# Elkapod_power_supply_conveter_module.net
KiCad netlist of a schematic drawn in Altium Designer
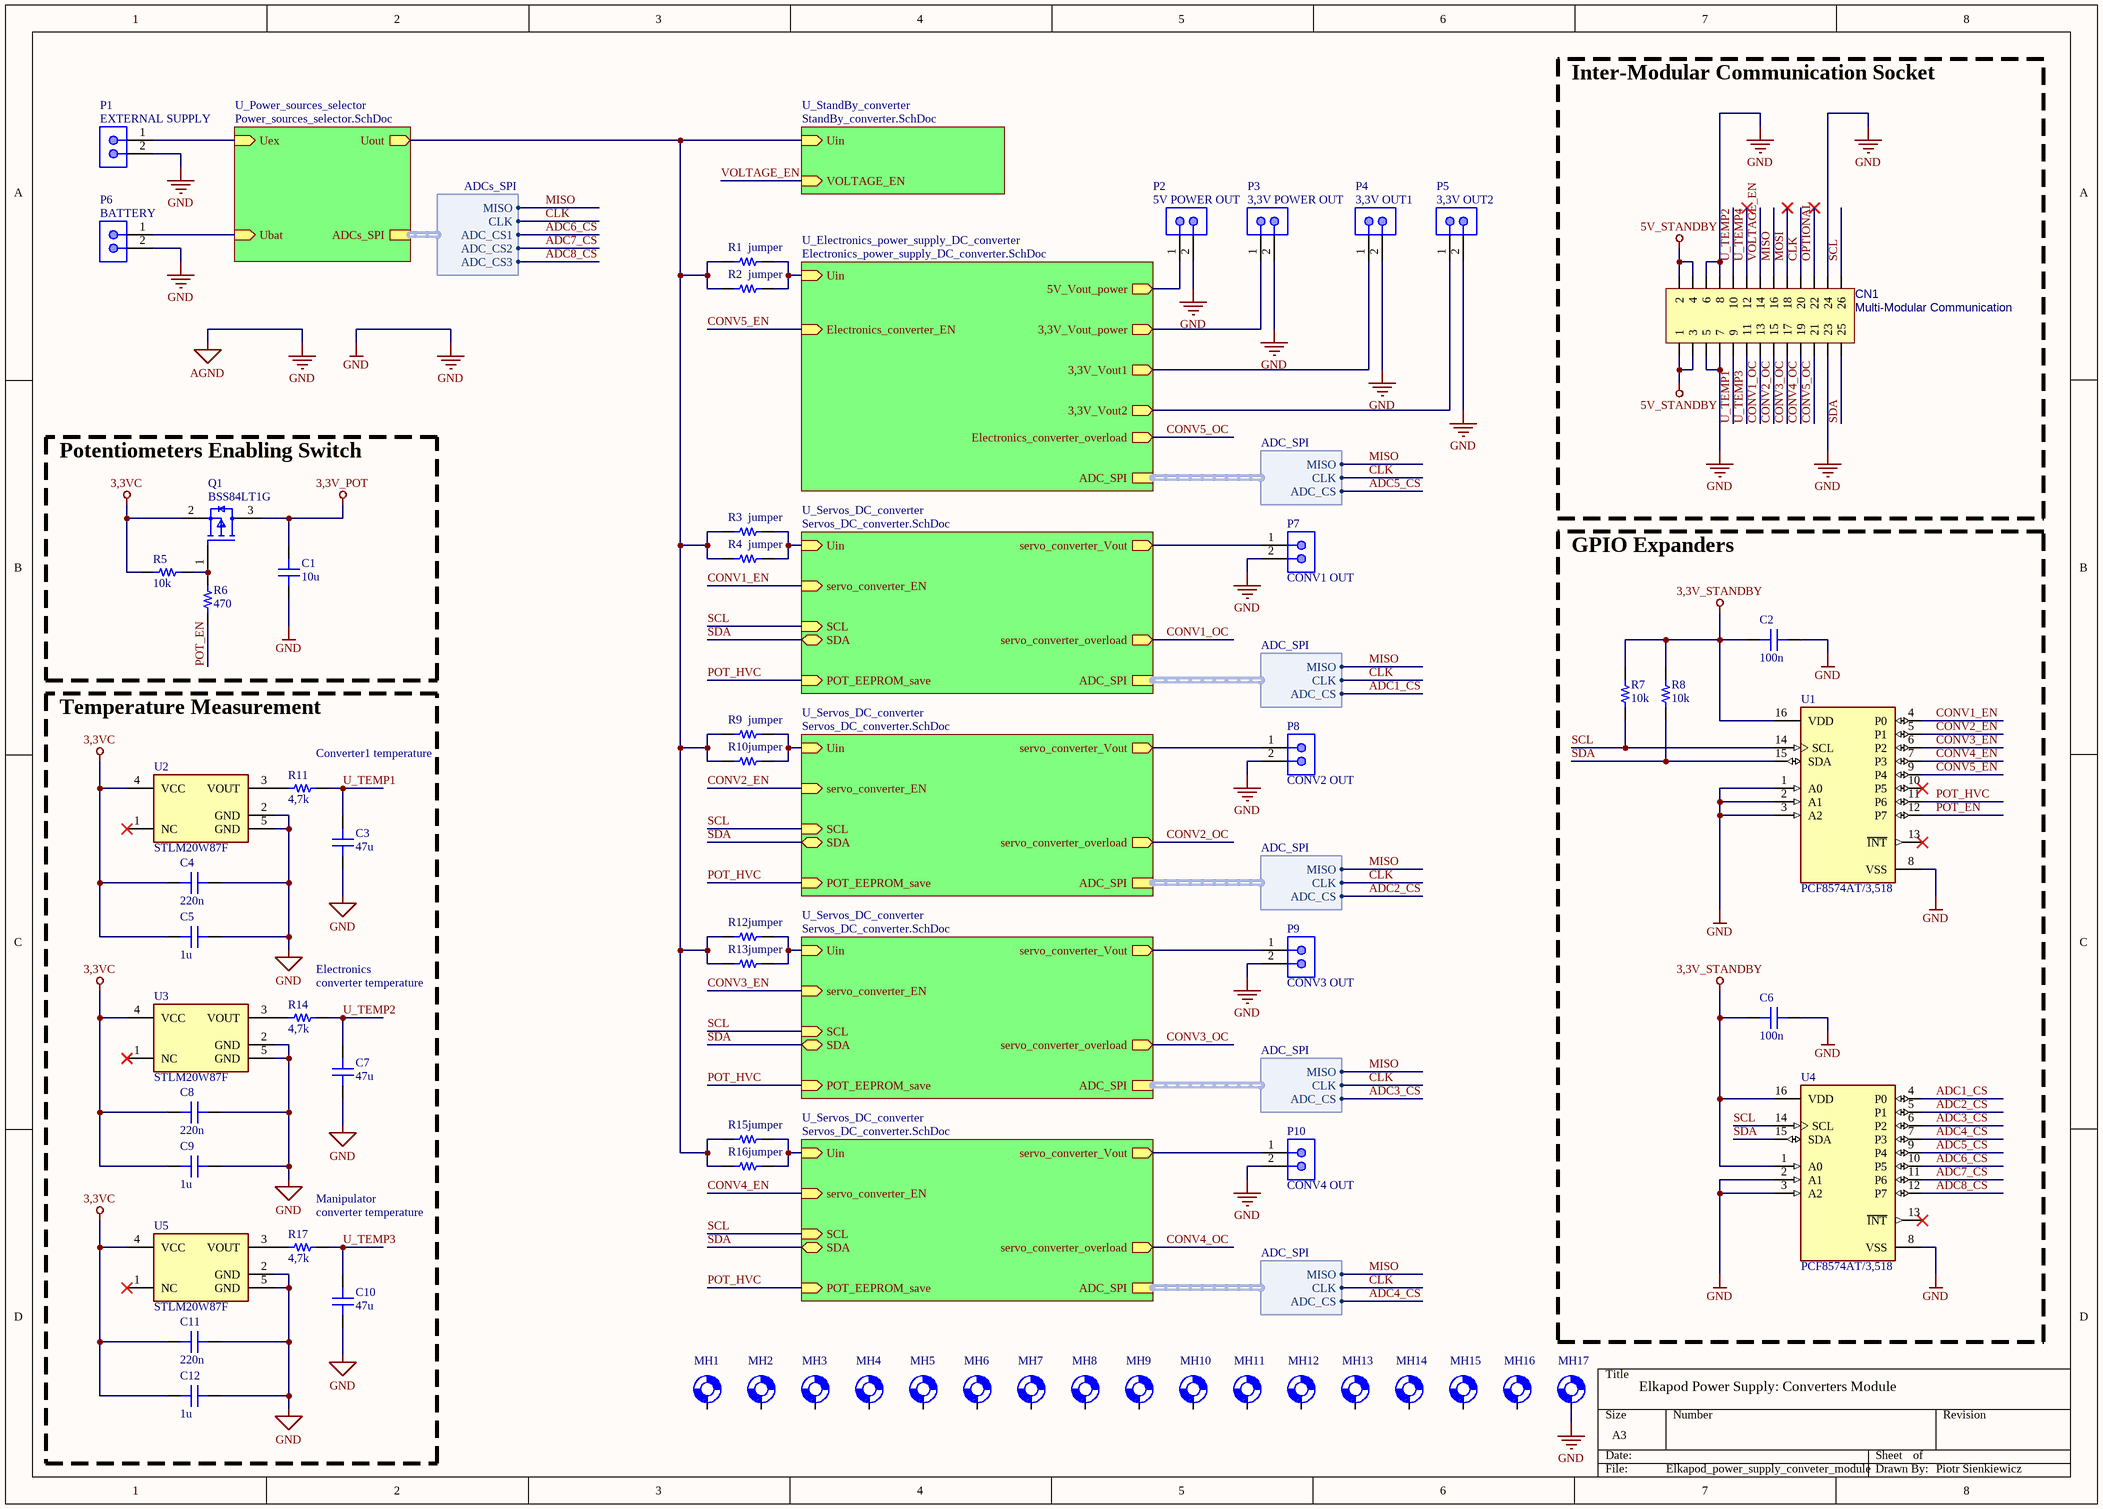
[diagram p0: Elkapod_power_supply_conveter_module.SchDoc]

(export (version "E")
  (design (tool "Eeschema 10.0.6"))
  (components
    (comp (ref "C1")
      (value "10u")
      (footprint "CAP 0603_1608")
      (description "CAP CER 10uF 35V X5R 0603")
      (fields (field (name "PART NUMBER") "C0603C272F3GAC7867") (field (name "MANUFACTURER") "KEMET"))
      (libsource (lib "Celestial Altium Library - altium_library") (part "Capacitor"))
    )
    (comp (ref "C2")
      (value "100n")
      (footprint "CAP 0603_1608")
      (description "CAP CER 100nF 25V X5R 0603")
      (fields (field (name "PART NUMBER") "C0603C272F3GAC7867") (field (name "MANUFACTURER") "KEMET"))
      (libsource (lib "Celestial Altium Library - altium_library") (part "Capacitor"))
    )
    (comp (ref "C3")
      (value "47u")
      (footprint "CAP 0603_1608")
      (description "CAP CER 47uF 6,3V X5R 0603")
      (fields (field (name "PART NUMBER") "C0603C272F3GAC7867") (field (name "MANUFACTURER") "KEMET"))
      (libsource (lib "Celestial Altium Library - altium_library") (part "Capacitor"))
    )
    (comp (ref "C4")
      (value "220n")
      (footprint "CAP 0603_1608")
      (description "CAP CER 220nF 25V X5R 0603")
      (fields (field (name "PART NUMBER") "C0603C272F3GAC7867") (field (name "MANUFACTURER") "KEMET"))
      (libsource (lib "Celestial Altium Library - altium_library") (part "Capacitor"))
    )
    (comp (ref "C5")
      (value "1u")
      (footprint "CAP 0603_1608")
      (description "CAP CER 1uF 25V X5R 0603")
      (fields (field (name "PART NUMBER") "C0603C272F3GAC7867") (field (name "MANUFACTURER") "KEMET"))
      (libsource (lib "Celestial Altium Library - altium_library") (part "Capacitor"))
    )
    (comp (ref "C6")
      (value "100n")
      (footprint "CAP 0603_1608")
      (description "CAP CER 100nF 25V X5R 0603")
      (fields (field (name "PART NUMBER") "C0603C272F3GAC7867") (field (name "MANUFACTURER") "KEMET"))
      (libsource (lib "Celestial Altium Library - altium_library") (part "Capacitor"))
    )
    (comp (ref "C7")
      (value "47u")
      (footprint "CAP 0603_1608")
      (description "CAP CER 47uF 6,3V X5R 0603")
      (fields (field (name "PART NUMBER") "C0603C272F3GAC7867") (field (name "MANUFACTURER") "KEMET"))
      (libsource (lib "Celestial Altium Library - altium_library") (part "Capacitor"))
    )
    (comp (ref "C8")
      (value "220n")
      (footprint "CAP 0603_1608")
      (description "CAP CER 220nF 25V X5R 0603")
      (fields (field (name "PART NUMBER") "C0603C272F3GAC7867") (field (name "MANUFACTURER") "KEMET"))
      (libsource (lib "Celestial Altium Library - altium_library") (part "Capacitor"))
    )
    (comp (ref "C9")
      (value "1u")
      (footprint "CAP 0603_1608")
      (description "CAP CER 1uF 25V X5R 0603")
      (fields (field (name "PART NUMBER") "C0603C272F3GAC7867") (field (name "MANUFACTURER") "KEMET"))
      (libsource (lib "Celestial Altium Library - altium_library") (part "Capacitor"))
    )
    (comp (ref "C10")
      (value "47u")
      (footprint "CAP 0603_1608")
      (description "CAP CER 47uF 6,3V X5R 0603")
      (fields (field (name "PART NUMBER") "C0603C272F3GAC7867") (field (name "MANUFACTURER") "KEMET"))
      (libsource (lib "Celestial Altium Library - altium_library") (part "Capacitor"))
    )
    (comp (ref "C11")
      (value "220n")
      (footprint "CAP 0603_1608")
      (description "CAP CER 220nF 25V X5R 0603")
      (fields (field (name "PART NUMBER") "C0603C272F3GAC7867") (field (name "MANUFACTURER") "KEMET"))
      (libsource (lib "Celestial Altium Library - altium_library") (part "Capacitor"))
    )
    (comp (ref "C12")
      (value "1u")
      (footprint "CAP 0603_1608")
      (description "CAP CER 1uF 25V X5R 0603")
      (fields (field (name "PART NUMBER") "C0603C272F3GAC7867") (field (name "MANUFACTURER") "KEMET"))
      (libsource (lib "Celestial Altium Library - altium_library") (part "Capacitor"))
    )
    (comp (ref "CN1")
      (value "Multi-Modular Communication")
      (footprint "GP_13x2_F")
      (libsource (lib "goldpin_female") (part "CN_13x2"))
    )
    (comp (ref "MH1")
      (value "M3 Mounting Hole")
      (footprint "M3_MOUNTING_HOLE")
      (libsource (lib "My_mounting_components") (part "M3 Mounting Hole"))
    )
    (comp (ref "MH2")
      (value "M3 Mounting Hole")
      (footprint "M3_MOUNTING_HOLE")
      (libsource (lib "My_mounting_components") (part "M3 Mounting Hole"))
    )
    (comp (ref "MH3")
      (value "M3 Mounting Hole")
      (footprint "M3_MOUNTING_HOLE")
      (libsource (lib "My_mounting_components") (part "M3 Mounting Hole"))
    )
    (comp (ref "MH4")
      (value "M3 Mounting Hole")
      (footprint "M3_MOUNTING_HOLE")
      (libsource (lib "My_mounting_components") (part "M3 Mounting Hole"))
    )
    (comp (ref "MH5")
      (value "M3 Mounting Hole")
      (footprint "M3_MOUNTING_HOLE")
      (libsource (lib "My_mounting_components") (part "M3 Mounting Hole"))
    )
    (comp (ref "MH6")
      (value "M3 Mounting Hole")
      (footprint "M3_MOUNTING_HOLE")
      (libsource (lib "My_mounting_components") (part "M3 Mounting Hole"))
    )
    (comp (ref "MH7")
      (value "M3 Mounting Hole")
      (footprint "M3_MOUNTING_HOLE")
      (libsource (lib "My_mounting_components") (part "M3 Mounting Hole"))
    )
    (comp (ref "MH8")
      (value "M3 Mounting Hole")
      (footprint "M3_MOUNTING_HOLE")
      (libsource (lib "My_mounting_components") (part "M3 Mounting Hole"))
    )
    (comp (ref "MH9")
      (value "M3 Mounting Hole")
      (footprint "M3_MOUNTING_HOLE")
      (libsource (lib "My_mounting_components") (part "M3 Mounting Hole"))
    )
    (comp (ref "MH10")
      (value "M3 Mounting Hole")
      (footprint "M3_MOUNTING_HOLE")
      (libsource (lib "My_mounting_components") (part "M3 Mounting Hole"))
    )
    (comp (ref "MH11")
      (value "M3 Mounting Hole")
      (footprint "M3_MOUNTING_HOLE")
      (libsource (lib "My_mounting_components") (part "M3 Mounting Hole"))
    )
    (comp (ref "MH12")
      (value "M3 Mounting Hole")
      (footprint "M3_MOUNTING_HOLE")
      (libsource (lib "My_mounting_components") (part "M3 Mounting Hole"))
    )
    (comp (ref "MH13")
      (value "M3 Mounting Hole")
      (footprint "M3_MOUNTING_HOLE")
      (libsource (lib "My_mounting_components") (part "M3 Mounting Hole"))
    )
    (comp (ref "MH14")
      (value "M3 Mounting Hole")
      (footprint "M3_MOUNTING_HOLE")
      (libsource (lib "My_mounting_components") (part "M3 Mounting Hole"))
    )
    (comp (ref "MH15")
      (value "M3 Mounting Hole")
      (footprint "M3_MOUNTING_HOLE")
      (libsource (lib "My_mounting_components") (part "M3 Mounting Hole"))
    )
    (comp (ref "MH16")
      (value "M3 Mounting Hole")
      (footprint "M3_MOUNTING_HOLE")
      (libsource (lib "My_mounting_components") (part "M3 Mounting Hole"))
    )
    (comp (ref "MH17")
      (value "M3 Mounting Hole")
      (footprint "M3_MOUNTING_HOLE")
      (libsource (lib "My_mounting_components") (part "M3 Mounting Hole"))
    )
    (comp (ref "P1")
      (value "EXTERNAL SUPPLY")
      (footprint "XT60PB-M")
      (description "XT60UPB-M; 30A/500V straight female DC PCB socket (pin1 -> +, pin2 -> -)")
      (libsource (lib "My_sockets") (part "XT60PB-M"))
    )
    (comp (ref "P2")
      (value "5V POWER OUT")
      (footprint "2x2,5mm2_WIRE")
      (description "2x2,5mm2 wire pads")
      (libsource (lib "") (part "2X2,5mm2_WIRE_1"))
    )
    (comp (ref "P3")
      (value "3,3V POWER OUT")
      (footprint "2x2,5mm2_WIRE")
      (description "2x2,5mm2 wire pads")
      (libsource (lib "") (part "2X2,5mm2_WIRE_1"))
    )
    (comp (ref "P4")
      (value "3,3V OUT1")
      (footprint "2x2,5mm2_WIRE")
      (description "2x2,5mm2 wire pads")
      (libsource (lib "") (part "2X2,5mm2_WIRE_1"))
    )
    (comp (ref "P5")
      (value "3,3V OUT2")
      (footprint "2x2,5mm2_WIRE")
      (description "2x2,5mm2 wire pads")
      (libsource (lib "") (part "2X2,5mm2_WIRE_1"))
    )
    (comp (ref "P6")
      (value "BATTERY")
      (footprint "XT60PB-M")
      (description "XT60UPB-M; 30A/500V straight female DC PCB socket (pin1 -> +, pin2 -> -)")
      (libsource (lib "My_sockets") (part "XT60PB-M"))
    )
    (comp (ref "P7")
      (value "CONV1 OUT")
      (footprint "2x2,5mm2_WIRE")
      (description "2x2,5mm2 wire pads")
      (libsource (lib "My_sockets") (part "2X2,5mm2_WIRE"))
    )
    (comp (ref "P8")
      (value "CONV2 OUT")
      (footprint "2x2,5mm2_WIRE")
      (description "2x2,5mm2 wire pads")
      (libsource (lib "My_sockets") (part "2X2,5mm2_WIRE"))
    )
    (comp (ref "P9")
      (value "CONV3 OUT")
      (footprint "2x2,5mm2_WIRE")
      (description "2x2,5mm2 wire pads")
      (libsource (lib "My_sockets") (part "2X2,5mm2_WIRE"))
    )
    (comp (ref "P10")
      (value "CONV4 OUT")
      (footprint "2x2,5mm2_WIRE")
      (description "2x2,5mm2 wire pads")
      (libsource (lib "My_sockets") (part "2X2,5mm2_WIRE"))
    )
    (comp (ref "Q1")
      (value "BSS84LT1G")
      (footprint "FP-318-08-IPC_A")
      (description "MOSFET P-CH 50V 130MA SOT-23")
      (libsource (lib "Altium Content Vault") (part "1317a8eff0fddff9cd18bdaa032127a"))
    )
    (comp (ref "R1")
      (value "jumper")
      (footprint "STACKPOLE CSM2512")
      (description "RES 0 OHM 1W 2512")
      (fields
        (field (name "PART NUMBER") "CSM2512FT20L0")
        (field (name "MANUFACTURER") "Stackpole Electronics Inc")
      )
      (libsource (lib "Celestial Altium Library - altium_library") (part "Resistor"))
    )
    (comp (ref "R2")
      (value "jumper")
      (footprint "STACKPOLE CSM2512")
      (description "RES 0 OHM 1W 2512")
      (fields
        (field (name "PART NUMBER") "CSM2512FT20L0")
        (field (name "MANUFACTURER") "Stackpole Electronics Inc")
      )
      (libsource (lib "Celestial Altium Library - altium_library") (part "Resistor"))
    )
    (comp (ref "R3")
      (value "jumper")
      (footprint "STACKPOLE CSM2512")
      (description "RES 0 OHM 1W 2512")
      (fields
        (field (name "PART NUMBER") "CSM2512FT20L0")
        (field (name "MANUFACTURER") "Stackpole Electronics Inc")
      )
      (libsource (lib "Celestial Altium Library - altium_library") (part "Resistor"))
    )
    (comp (ref "R4")
      (value "jumper")
      (footprint "STACKPOLE CSM2512")
      (description "RES 0 OHM 1W 2512")
      (fields
        (field (name "PART NUMBER") "CSM2512FT20L0")
        (field (name "MANUFACTURER") "Stackpole Electronics Inc")
      )
      (libsource (lib "Celestial Altium Library - altium_library") (part "Resistor"))
    )
    (comp (ref "R5")
      (value "10k")
      (footprint "RES 0603_1608")
      (description "RES 10K OHM 1% 0,1W 0603")
      (fields
        (field (name "PART NUMBER") "RNCS0603BKE10K0")
        (field (name "MANUFACTURER") "Stackpole Electronics Inc")
      )
      (libsource (lib "Celestial Altium Library - altium_library") (part "Resistor"))
    )
    (comp (ref "R6")
      (value "470")
      (footprint "RES 0603_1608")
      (description "RES 470 OHM 1% 0,1W 0603")
      (fields
        (field (name "PART NUMBER") "RNCS0603BKE10K0")
        (field (name "MANUFACTURER") "Stackpole Electronics Inc")
      )
      (libsource (lib "Celestial Altium Library - altium_library") (part "Resistor"))
    )
    (comp (ref "R7")
      (value "10k")
      (footprint "RES 0603_1608")
      (description "RES 10K OHM 1% 0,1W 0603")
      (fields
        (field (name "PART NUMBER") "RNCS0603BKE10K0")
        (field (name "MANUFACTURER") "Stackpole Electronics Inc")
      )
      (libsource (lib "Celestial Altium Library - altium_library") (part "Resistor"))
    )
    (comp (ref "R8")
      (value "10k")
      (footprint "RES 0603_1608")
      (description "RES 10K OHM 1% 0,1W 0603")
      (fields
        (field (name "PART NUMBER") "RNCS0603BKE10K0")
        (field (name "MANUFACTURER") "Stackpole Electronics Inc")
      )
      (libsource (lib "Celestial Altium Library - altium_library") (part "Resistor"))
    )
    (comp (ref "R9")
      (value "jumper")
      (footprint "STACKPOLE CSM2512")
      (description "RES 0 OHM 1W 2512")
      (fields
        (field (name "PART NUMBER") "CSM2512FT20L0")
        (field (name "MANUFACTURER") "Stackpole Electronics Inc")
      )
      (libsource (lib "Celestial Altium Library - altium_library") (part "Resistor"))
    )
    (comp (ref "R10")
      (value "jumper")
      (footprint "STACKPOLE CSM2512")
      (description "RES 0 OHM 1W 2512")
      (fields
        (field (name "PART NUMBER") "CSM2512FT20L0")
        (field (name "MANUFACTURER") "Stackpole Electronics Inc")
      )
      (libsource (lib "Celestial Altium Library - altium_library") (part "Resistor"))
    )
    (comp (ref "R11")
      (value "4,7k")
      (footprint "RES 0603_1608")
      (description "RES 4,7K OHM 1% 0,1W 0603")
      (fields
        (field (name "PART NUMBER") "RNCS0603BKE10K0")
        (field (name "MANUFACTURER") "Stackpole Electronics Inc")
      )
      (libsource (lib "Celestial Altium Library - altium_library") (part "Resistor"))
    )
    (comp (ref "R12")
      (value "jumper")
      (footprint "STACKPOLE CSM2512")
      (description "RES 0 OHM 1W 2512")
      (fields
        (field (name "PART NUMBER") "CSM2512FT20L0")
        (field (name "MANUFACTURER") "Stackpole Electronics Inc")
      )
      (libsource (lib "Celestial Altium Library - altium_library") (part "Resistor"))
    )
    (comp (ref "R13")
      (value "jumper")
      (footprint "STACKPOLE CSM2512")
      (description "RES 0 OHM 1W 2512")
      (fields
        (field (name "PART NUMBER") "CSM2512FT20L0")
        (field (name "MANUFACTURER") "Stackpole Electronics Inc")
      )
      (libsource (lib "Celestial Altium Library - altium_library") (part "Resistor"))
    )
    (comp (ref "R14")
      (value "4,7k")
      (footprint "RES 0603_1608")
      (description "RES 4,7K OHM 1% 0,1W 0603")
      (fields
        (field (name "PART NUMBER") "RNCS0603BKE10K0")
        (field (name "MANUFACTURER") "Stackpole Electronics Inc")
      )
      (libsource (lib "Celestial Altium Library - altium_library") (part "Resistor"))
    )
    (comp (ref "R15")
      (value "jumper")
      (footprint "STACKPOLE CSM2512")
      (description "RES 0 OHM 1W 2512")
      (fields
        (field (name "PART NUMBER") "CSM2512FT20L0")
        (field (name "MANUFACTURER") "Stackpole Electronics Inc")
      )
      (libsource (lib "Celestial Altium Library - altium_library") (part "Resistor"))
    )
    (comp (ref "R16")
      (value "jumper")
      (footprint "STACKPOLE CSM2512")
      (description "RES 0 OHM 1W 2512")
      (fields
        (field (name "PART NUMBER") "CSM2512FT20L0")
        (field (name "MANUFACTURER") "Stackpole Electronics Inc")
      )
      (libsource (lib "Celestial Altium Library - altium_library") (part "Resistor"))
    )
    (comp (ref "R17")
      (value "4,7k")
      (footprint "RES 0603_1608")
      (description "RES 4,7K OHM 1% 0,1W 0603")
      (fields
        (field (name "PART NUMBER") "RNCS0603BKE10K0")
        (field (name "MANUFACTURER") "Stackpole Electronics Inc")
      )
      (libsource (lib "Celestial Altium Library - altium_library") (part "Resistor"))
    )
    (comp (ref "U1")
      (value "PCF8574AT/3,518")
      (footprint "FP-SOT162-1-MFG")
      (description "IC I/O EXPANDER I2C 8B 16SOIC")
      (fields
        (field (name "MANUFACTURER") "NXP Semiconductors")
        (field (name "OCTOPART") "https://octopart.com/pcf8574at%2F3%2C518-nxp+semiconductors-11541925")
      )
      (libsource (lib "Altium Content Vault") (part "f7fde53ce59de981fb0b266a4e103eb"))
    )
    (comp (ref "U2")
      (value "STLM20W87F")
      (footprint "FP-SOT323-5L-7091413-MFG")
      (description "SENSOR ANALOG -55C-130C SOT323-5")
      (fields
        (field (name "MANUFACTURER") "STMicroelectronics")
        (field (name "OCTOPART") "https://octopart.com/stlm20w87f-stmicroelectronics-4006294")
      )
      (libsource (lib "Altium Content Vault") (part "0e0d9f6345b04f04d846d3fd79e931c"))
    )
    (comp (ref "U3")
      (value "STLM20W87F")
      (footprint "FP-SOT323-5L-7091413-MFG")
      (description "SENSOR ANALOG -55C-130C SOT323-5")
      (fields
        (field (name "MANUFACTURER") "STMicroelectronics")
        (field (name "OCTOPART") "https://octopart.com/stlm20w87f-stmicroelectronics-4006294")
      )
      (libsource (lib "Altium Content Vault") (part "0e0d9f6345b04f04d846d3fd79e931c"))
    )
    (comp (ref "U4")
      (value "PCF8574AT/3,518")
      (footprint "FP-SOT162-1-MFG")
      (description "IC I/O EXPANDER I2C 8B 16SOIC")
      (fields
        (field (name "MANUFACTURER") "NXP Semiconductors")
        (field (name "OCTOPART") "https://octopart.com/pcf8574at%2F3%2C518-nxp+semiconductors-11541925")
      )
      (libsource (lib "Altium Content Vault") (part "f7fde53ce59de981fb0b266a4e103eb"))
    )
    (comp (ref "U5")
      (value "STLM20W87F")
      (footprint "FP-SOT323-5L-7091413-MFG")
      (description "SENSOR ANALOG -55C-130C SOT323-5")
      (fields
        (field (name "MANUFACTURER") "STMicroelectronics")
        (field (name "OCTOPART") "https://octopart.com/stlm20w87f-stmicroelectronics-4006294")
      )
      (libsource (lib "Altium Content Vault") (part "0e0d9f6345b04f04d846d3fd79e931c"))
    )
  )
  (nets
    (net (code "3") (name "/3,3V_Vout1") (class "Default")
      (node (ref "P4") (pin "1") (pinfunction "+_1") (pintype "passive"))
    )
    (net (code "4") (name "/3,3V_Vout2") (class "Default")
      (node (ref "P5") (pin "1") (pinfunction "+_1") (pintype "passive"))
    )
    (net (code "5") (name "/3,3V_Vout_power") (class "Default")
      (node (ref "P3") (pin "1") (pinfunction "+_1") (pintype "passive"))
    )
    (net (code "6") (name "/5V_Vout_power") (class "Default")
      (node (ref "P2") (pin "1") (pinfunction "+_1") (pintype "passive"))
    )
    (net (code "7") (name "/ADC1_CS") (class "Default")
      (node (ref "U4") (pin "4") (pinfunction "P0_4") (pintype "bidirectional"))
    )
    (net (code "8") (name "/ADC2_CS") (class "Default")
      (node (ref "U4") (pin "5") (pinfunction "P1_5") (pintype "bidirectional"))
    )
    (net (code "9") (name "/ADC3_CS") (class "Default")
      (node (ref "U4") (pin "6") (pinfunction "P2_6") (pintype "bidirectional"))
    )
    (net (code "10") (name "/ADC4_CS") (class "Default")
      (node (ref "U4") (pin "7") (pinfunction "P3_7") (pintype "bidirectional"))
    )
    (net (code "11") (name "/ADC5_CS") (class "Default")
      (node (ref "U4") (pin "9") (pinfunction "P4_9") (pintype "bidirectional"))
    )
    (net (code "12") (name "/ADC6_CS") (class "Default")
      (node (ref "U4") (pin "10") (pinfunction "P5_10") (pintype "bidirectional"))
    )
    (net (code "13") (name "/ADC7_CS") (class "Default")
      (node (ref "U4") (pin "11") (pinfunction "P6_11") (pintype "bidirectional"))
    )
    (net (code "14") (name "/ADC8_CS") (class "Default")
      (node (ref "U4") (pin "12") (pinfunction "P7_12") (pintype "bidirectional"))
    )
    (net (code "15") (name "/CLK") (class "Default")
      (node (ref "CN1") (pin "20") (pinfunction "20_20") (pintype "passive"))
    )
    (net (code "16") (name "/CONV1_EN") (class "Default")
      (node (ref "U1") (pin "4") (pinfunction "P0_4") (pintype "bidirectional"))
    )
    (net (code "17") (name "/CONV1_OC") (class "Default")
      (node (ref "CN1") (pin "13") (pinfunction "13_13") (pintype "passive"))
    )
    (net (code "18") (name "/CONV2_EN") (class "Default")
      (node (ref "U1") (pin "5") (pinfunction "P1_5") (pintype "bidirectional"))
    )
    (net (code "19") (name "/CONV2_OC") (class "Default")
      (node (ref "CN1") (pin "15") (pinfunction "15_15") (pintype "passive"))
    )
    (net (code "20") (name "/CONV3_EN") (class "Default")
      (node (ref "U1") (pin "6") (pinfunction "P2_6") (pintype "bidirectional"))
    )
    (net (code "21") (name "/CONV3_OC") (class "Default")
      (node (ref "CN1") (pin "17") (pinfunction "17_17") (pintype "passive"))
    )
    (net (code "22") (name "/CONV4_EN") (class "Default")
      (node (ref "U1") (pin "7") (pinfunction "P3_7") (pintype "bidirectional"))
    )
    (net (code "23") (name "/CONV4_OC") (class "Default")
      (node (ref "CN1") (pin "19") (pinfunction "19_19") (pintype "passive"))
    )
    (net (code "24") (name "/CONV5_EN") (class "Default")
      (node (ref "U1") (pin "9") (pinfunction "P4_9") (pintype "bidirectional"))
    )
    (net (code "25") (name "/CONV5_OC") (class "Default")
      (node (ref "CN1") (pin "21") (pinfunction "21_21") (pintype "passive"))
    )
    (net (code "26") (name "/MISO") (class "Default")
      (node (ref "CN1") (pin "16") (pinfunction "16_16") (pintype "passive"))
    )
    (net (code "27") (name "/MOSI") (class "Default")
      (node (ref "CN1") (pin "18") (pinfunction "18_18") (pintype "passive+no_connect"))
    )
    (net (code "28") (name "/OPTIONAL") (class "Default")
      (node (ref "CN1") (pin "22") (pinfunction "22_22") (pintype "passive+no_connect"))
    )
    (net (code "29") (name "/POT_EN") (class "Default")
      (node (ref "R6") (pin "2") (pinfunction "2_2") (pintype "passive"))
      (node (ref "U1") (pin "12") (pinfunction "P7_12") (pintype "bidirectional"))
    )
    (net (code "30") (name "/POT_HVC") (class "Default")
      (node (ref "U1") (pin "11") (pinfunction "P6_11") (pintype "bidirectional"))
    )
    (net (code "31") (name "/SCL") (class "Default")
      (node (ref "CN1") (pin "26") (pinfunction "26_26") (pintype "passive"))
      (node (ref "R7") (pin "1") (pinfunction "1_1") (pintype "passive"))
      (node (ref "U1") (pin "14") (pinfunction "SCL_14") (pintype "input"))
      (node (ref "U4") (pin "14") (pinfunction "SCL_14") (pintype "input"))
    )
    (net (code "32") (name "/SDA") (class "Default")
      (node (ref "CN1") (pin "25") (pinfunction "25_25") (pintype "passive"))
      (node (ref "R8") (pin "1") (pinfunction "1_1") (pintype "passive"))
      (node (ref "U1") (pin "15") (pinfunction "SDA_15") (pintype "bidirectional"))
      (node (ref "U4") (pin "15") (pinfunction "SDA_15") (pintype "bidirectional"))
    )
    (net (code "33") (name "/U_TEMP1") (class "Default")
      (node (ref "C3") (pin "2") (pinfunction "2_2") (pintype "passive"))
      (node (ref "CN1") (pin "9") (pinfunction "9_9") (pintype "passive"))
      (node (ref "R11") (pin "2") (pinfunction "2_2") (pintype "passive"))
    )
    (net (code "34") (name "/U_TEMP2") (class "Default")
      (node (ref "C7") (pin "2") (pinfunction "2_2") (pintype "passive"))
      (node (ref "CN1") (pin "10") (pinfunction "10_10") (pintype "passive"))
      (node (ref "R14") (pin "2") (pinfunction "2_2") (pintype "passive"))
    )
    (net (code "35") (name "/U_TEMP3") (class "Default")
      (node (ref "C10") (pin "2") (pinfunction "2_2") (pintype "passive"))
      (node (ref "CN1") (pin "11") (pinfunction "11_11") (pintype "passive"))
      (node (ref "R17") (pin "2") (pinfunction "2_2") (pintype "passive"))
    )
    (net (code "36") (name "/U_TEMP4") (class "Default")
      (node (ref "CN1") (pin "12") (pinfunction "12_12") (pintype "passive+no_connect"))
    )
    (net (code "37") (name "/Ubat") (class "Default")
      (node (ref "P6") (pin "1") (pinfunction "+_1") (pintype "passive"))
    )
    (net (code "38") (name "/Uex") (class "Default")
      (node (ref "P1") (pin "1") (pinfunction "+_1") (pintype "passive"))
    )
    (net (code "39") (name "/Uin") (class "Default")
      (node (ref "R1") (pin "1") (pinfunction "1_1") (pintype "passive"))
      (node (ref "R2") (pin "1") (pinfunction "1_1") (pintype "passive"))
    )
    (net (code "40") (name "/Uin_1") (class "Default")
      (node (ref "R3") (pin "1") (pinfunction "1_1") (pintype "passive"))
      (node (ref "R4") (pin "1") (pinfunction "1_1") (pintype "passive"))
    )
    (net (code "41") (name "/Uin_2") (class "Default")
      (node (ref "R12") (pin "1") (pinfunction "1_1") (pintype "passive"))
      (node (ref "R13") (pin "1") (pinfunction "1_1") (pintype "passive"))
    )
    (net (code "42") (name "/Uin_3") (class "Default")
      (node (ref "R15") (pin "1") (pinfunction "1_1") (pintype "passive"))
      (node (ref "R16") (pin "1") (pinfunction "1_1") (pintype "passive"))
    )
    (net (code "43") (name "/Uin_4") (class "Default")
      (node (ref "R10") (pin "1") (pinfunction "1_1") (pintype "passive"))
      (node (ref "R9") (pin "1") (pinfunction "1_1") (pintype "passive"))
    )
    (net (code "44") (name "/Uout") (class "Default")
      (node (ref "R1") (pin "2") (pinfunction "2_2") (pintype "passive"))
      (node (ref "R10") (pin "2") (pinfunction "2_2") (pintype "passive"))
      (node (ref "R12") (pin "2") (pinfunction "2_2") (pintype "passive"))
      (node (ref "R13") (pin "2") (pinfunction "2_2") (pintype "passive"))
      (node (ref "R15") (pin "2") (pinfunction "2_2") (pintype "passive"))
      (node (ref "R16") (pin "2") (pinfunction "2_2") (pintype "passive"))
      (node (ref "R2") (pin "2") (pinfunction "2_2") (pintype "passive"))
      (node (ref "R3") (pin "2") (pinfunction "2_2") (pintype "passive"))
      (node (ref "R4") (pin "2") (pinfunction "2_2") (pintype "passive"))
      (node (ref "R9") (pin "2") (pinfunction "2_2") (pintype "passive"))
    )
    (net (code "45") (name "/VOLTAGE_EN") (class "Default")
      (node (ref "CN1") (pin "14") (pinfunction "14_14") (pintype "passive"))
    )
    (net (code "46") (name "/servo_converter_Vout") (class "Default")
      (node (ref "P10") (pin "1") (pinfunction "+_1") (pintype "passive"))
    )
    (net (code "47") (name "/servo_converter_Vout_1") (class "Default")
      (node (ref "P9") (pin "1") (pinfunction "+_1") (pintype "passive"))
    )
    (net (code "48") (name "/servo_converter_Vout_2") (class "Default")
      (node (ref "P7") (pin "1") (pinfunction "+_1") (pintype "passive"))
    )
    (net (code "49") (name "/servo_converter_Vout_3") (class "Default")
      (node (ref "P8") (pin "1") (pinfunction "+_1") (pintype "passive"))
    )
    (net (code "52") (name "3,3VC") (class "Default")
      (node (ref "C11") (pin "2") (pinfunction "2_2") (pintype "passive"))
      (node (ref "C12") (pin "2") (pinfunction "2_2") (pintype "passive"))
      (node (ref "C4") (pin "2") (pinfunction "2_2") (pintype "passive"))
      (node (ref "C5") (pin "2") (pinfunction "2_2") (pintype "passive"))
      (node (ref "C8") (pin "2") (pinfunction "2_2") (pintype "passive"))
      (node (ref "C9") (pin "2") (pinfunction "2_2") (pintype "passive"))
      (node (ref "Q1") (pin "2") (pinfunction "S_2") (pintype "passive"))
      (node (ref "R5") (pin "1") (pinfunction "1_1") (pintype "passive"))
      (node (ref "U2") (pin "4") (pinfunction "VCC_4") (pintype "power_in"))
      (node (ref "U3") (pin "4") (pinfunction "VCC_4") (pintype "power_in"))
      (node (ref "U5") (pin "4") (pinfunction "VCC_4") (pintype "power_in"))
    )
    (net (code "53") (name "3,3V_POT") (class "Default")
      (node (ref "C1") (pin "2") (pinfunction "2_2") (pintype "passive"))
      (node (ref "Q1") (pin "3") (pinfunction "D_3") (pintype "passive"))
    )
    (net (code "54") (name "3,3V_STANDBY") (class "Default")
      (node (ref "C2") (pin "2") (pinfunction "2_2") (pintype "passive"))
      (node (ref "C6") (pin "2") (pinfunction "2_2") (pintype "passive"))
      (node (ref "R7") (pin "2") (pinfunction "2_2") (pintype "passive"))
      (node (ref "R8") (pin "2") (pinfunction "2_2") (pintype "passive"))
      (node (ref "U1") (pin "16") (pinfunction "VDD_16") (pintype "power_in"))
      (node (ref "U4") (pin "1") (pinfunction "A0_1") (pintype "input"))
      (node (ref "U4") (pin "16") (pinfunction "VDD_16") (pintype "power_in"))
    )
    (net (code "55") (name "5V_STANDBY") (class "Default")
      (node (ref "CN1") (pin "1") (pinfunction "1_1") (pintype "passive"))
      (node (ref "CN1") (pin "2") (pinfunction "2_2") (pintype "passive"))
      (node (ref "CN1") (pin "3") (pinfunction "3_3") (pintype "passive"))
      (node (ref "CN1") (pin "4") (pinfunction "4_4") (pintype "passive"))
    )
    (net (code "56") (name "AGND") (class "Default")
      (node (ref "C1") (pin "1") (pinfunction "1_1") (pintype "passive"))
      (node (ref "C10") (pin "1") (pinfunction "1_1") (pintype "passive"))
      (node (ref "C11") (pin "1") (pinfunction "1_1") (pintype "passive"))
      (node (ref "C12") (pin "1") (pinfunction "1_1") (pintype "passive"))
      (node (ref "C2") (pin "1") (pinfunction "1_1") (pintype "passive"))
      (node (ref "C3") (pin "1") (pinfunction "1_1") (pintype "passive"))
      (node (ref "C4") (pin "1") (pinfunction "1_1") (pintype "passive"))
      (node (ref "C5") (pin "1") (pinfunction "1_1") (pintype "passive"))
      (node (ref "C6") (pin "1") (pinfunction "1_1") (pintype "passive"))
      (node (ref "C7") (pin "1") (pinfunction "1_1") (pintype "passive"))
      (node (ref "C8") (pin "1") (pinfunction "1_1") (pintype "passive"))
      (node (ref "C9") (pin "1") (pinfunction "1_1") (pintype "passive"))
      (node (ref "CN1") (pin "23") (pinfunction "23_23") (pintype "passive"))
      (node (ref "CN1") (pin "24") (pinfunction "24_24") (pintype "passive"))
      (node (ref "CN1") (pin "5") (pinfunction "5_5") (pintype "passive"))
      (node (ref "CN1") (pin "6") (pinfunction "6_6") (pintype "passive"))
      (node (ref "CN1") (pin "7") (pinfunction "7_7") (pintype "passive"))
      (node (ref "CN1") (pin "8") (pinfunction "8_8") (pintype "passive"))
      (node (ref "MH17") (pin "1") (pinfunction "1_1") (pintype "passive"))
      (node (ref "P1") (pin "2") (pinfunction "-_2") (pintype "passive"))
      (node (ref "P10") (pin "2") (pinfunction "-_2") (pintype "passive"))
      (node (ref "P2") (pin "2") (pinfunction "-_2") (pintype "passive"))
      (node (ref "P3") (pin "2") (pinfunction "-_2") (pintype "passive"))
      (node (ref "P4") (pin "2") (pinfunction "-_2") (pintype "passive"))
      (node (ref "P5") (pin "2") (pinfunction "-_2") (pintype "passive"))
      (node (ref "P6") (pin "2") (pinfunction "-_2") (pintype "passive"))
      (node (ref "P7") (pin "2") (pinfunction "-_2") (pintype "passive"))
      (node (ref "P8") (pin "2") (pinfunction "-_2") (pintype "passive"))
      (node (ref "P9") (pin "2") (pinfunction "-_2") (pintype "passive"))
      (node (ref "U1") (pin "1") (pinfunction "A0_1") (pintype "input"))
      (node (ref "U1") (pin "2") (pinfunction "A1_2") (pintype "input"))
      (node (ref "U1") (pin "3") (pinfunction "A2_3") (pintype "input"))
      (node (ref "U1") (pin "8") (pinfunction "VSS_8") (pintype "power_in"))
      (node (ref "U2") (pin "2") (pinfunction "GND_2") (pintype "power_in"))
      (node (ref "U2") (pin "5") (pinfunction "GND_5") (pintype "power_in"))
      (node (ref "U3") (pin "2") (pinfunction "GND_2") (pintype "power_in"))
      (node (ref "U3") (pin "5") (pinfunction "GND_5") (pintype "power_in"))
      (node (ref "U4") (pin "2") (pinfunction "A1_2") (pintype "input"))
      (node (ref "U4") (pin "3") (pinfunction "A2_3") (pintype "input"))
      (node (ref "U4") (pin "8") (pinfunction "VSS_8") (pintype "power_in"))
      (node (ref "U5") (pin "2") (pinfunction "GND_2") (pintype "power_in"))
      (node (ref "U5") (pin "5") (pinfunction "GND_5") (pintype "power_in"))
    )
    (net (code "57") (name "Net-(Q1-G)") (class "Default")
      (node (ref "Q1") (pin "1") (pinfunction "G_1") (pintype "passive"))
      (node (ref "R5") (pin "2") (pinfunction "2_2") (pintype "passive"))
      (node (ref "R6") (pin "1") (pinfunction "1_1") (pintype "passive"))
    )
    (net (code "58") (name "Net-(U2-VOUT)") (class "Default")
      (node (ref "R11") (pin "1") (pinfunction "1_1") (pintype "passive"))
      (node (ref "U2") (pin "3") (pinfunction "VOUT_3") (pintype "passive"))
    )
    (net (code "59") (name "Net-(U3-VOUT)") (class "Default")
      (node (ref "R14") (pin "1") (pinfunction "1_1") (pintype "passive"))
      (node (ref "U3") (pin "3") (pinfunction "VOUT_3") (pintype "passive"))
    )
    (net (code "60") (name "Net-(U5-VOUT)") (class "Default")
      (node (ref "R17") (pin "1") (pinfunction "1_1") (pintype "passive"))
      (node (ref "U5") (pin "3") (pinfunction "VOUT_3") (pintype "passive"))
    )
    (net (code "61") (name "unconnected-(MH1-Pad1)") (class "Default")
      (node (ref "MH1") (pin "1") (pinfunction "1_1") (pintype "passive"))
    )
    (net (code "62") (name "unconnected-(MH2-Pad1)") (class "Default")
      (node (ref "MH2") (pin "1") (pinfunction "1_1") (pintype "passive"))
    )
    (net (code "63") (name "unconnected-(MH3-Pad1)") (class "Default")
      (node (ref "MH3") (pin "1") (pinfunction "1_1") (pintype "passive"))
    )
    (net (code "64") (name "unconnected-(MH4-Pad1)") (class "Default")
      (node (ref "MH4") (pin "1") (pinfunction "1_1") (pintype "passive"))
    )
    (net (code "65") (name "unconnected-(MH5-Pad1)") (class "Default")
      (node (ref "MH5") (pin "1") (pinfunction "1_1") (pintype "passive"))
    )
    (net (code "66") (name "unconnected-(MH6-Pad1)") (class "Default")
      (node (ref "MH6") (pin "1") (pinfunction "1_1") (pintype "passive"))
    )
    (net (code "67") (name "unconnected-(MH7-Pad1)") (class "Default")
      (node (ref "MH7") (pin "1") (pinfunction "1_1") (pintype "passive"))
    )
    (net (code "68") (name "unconnected-(MH8-Pad1)") (class "Default")
      (node (ref "MH8") (pin "1") (pinfunction "1_1") (pintype "passive"))
    )
    (net (code "69") (name "unconnected-(MH9-Pad1)") (class "Default")
      (node (ref "MH9") (pin "1") (pinfunction "1_1") (pintype "passive"))
    )
    (net (code "70") (name "unconnected-(MH10-Pad1)") (class "Default")
      (node (ref "MH10") (pin "1") (pinfunction "1_1") (pintype "passive"))
    )
    (net (code "71") (name "unconnected-(MH11-Pad1)") (class "Default")
      (node (ref "MH11") (pin "1") (pinfunction "1_1") (pintype "passive"))
    )
    (net (code "72") (name "unconnected-(MH12-Pad1)") (class "Default")
      (node (ref "MH12") (pin "1") (pinfunction "1_1") (pintype "passive"))
    )
    (net (code "73") (name "unconnected-(MH13-Pad1)") (class "Default")
      (node (ref "MH13") (pin "1") (pinfunction "1_1") (pintype "passive"))
    )
    (net (code "74") (name "unconnected-(MH14-Pad1)") (class "Default")
      (node (ref "MH14") (pin "1") (pinfunction "1_1") (pintype "passive"))
    )
    (net (code "75") (name "unconnected-(MH15-Pad1)") (class "Default")
      (node (ref "MH15") (pin "1") (pinfunction "1_1") (pintype "passive"))
    )
    (net (code "76") (name "unconnected-(MH16-Pad1)") (class "Default")
      (node (ref "MH16") (pin "1") (pinfunction "1_1") (pintype "passive"))
    )
    (net (code "77") (name "unconnected-(U1-P5-Pad10)") (class "Default")
      (node (ref "U1") (pin "10") (pinfunction "P5_10") (pintype "bidirectional+no_connect"))
    )
    (net (code "78") (name "unconnected-(U1-~{INT}-Pad13)") (class "Default")
      (node (ref "U1") (pin "13") (pinfunction "~{INT}_13") (pintype "output+no_connect"))
    )
    (net (code "79") (name "unconnected-(U2-NC-Pad1)") (class "Default")
      (node (ref "U2") (pin "1") (pinfunction "NC_1") (pintype "passive+no_connect"))
    )
    (net (code "80") (name "unconnected-(U3-NC-Pad1)") (class "Default")
      (node (ref "U3") (pin "1") (pinfunction "NC_1") (pintype "passive+no_connect"))
    )
    (net (code "81") (name "unconnected-(U4-~{INT}-Pad13)") (class "Default")
      (node (ref "U4") (pin "13") (pinfunction "~{INT}_13") (pintype "output+no_connect"))
    )
    (net (code "82") (name "unconnected-(U5-NC-Pad1)") (class "Default")
      (node (ref "U5") (pin "1") (pinfunction "NC_1") (pintype "passive+no_connect"))
    )
  )
)
